# LEDs.net
KiCad netlist of a schematic drawn in Altium Designer
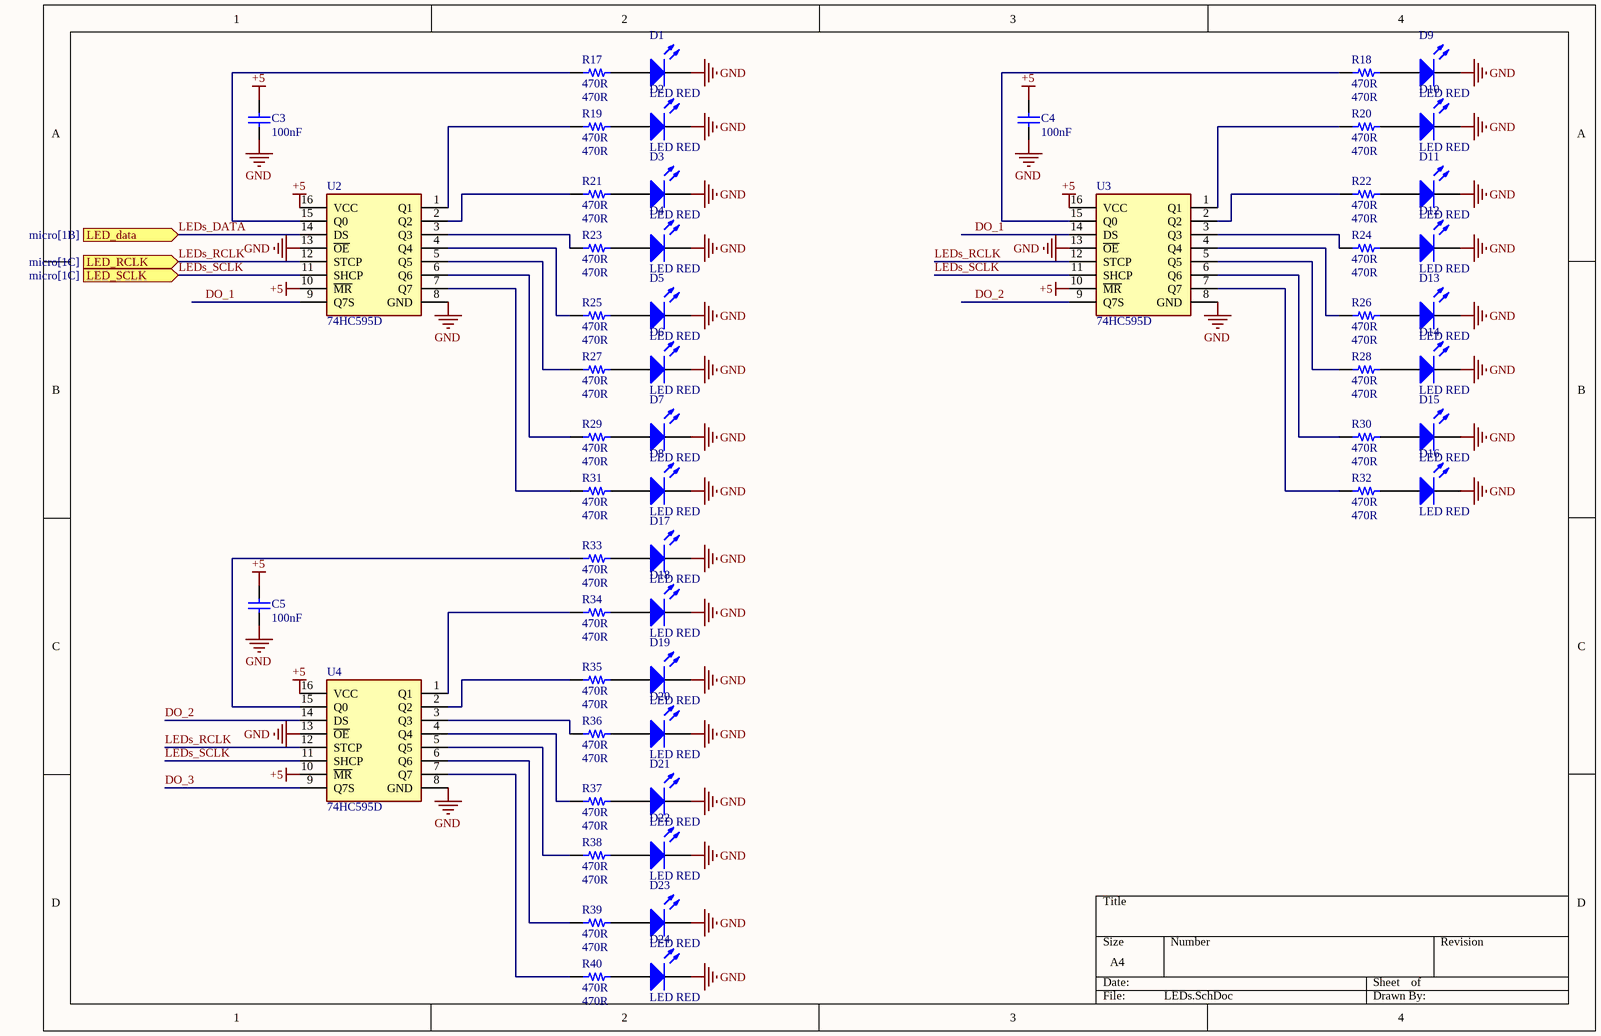
[diagram p0: LEDs.SchDoc]

(export (version "E")
  (design (tool "Eeschema 10.0.6"))
  (components
    (comp (ref "C3")
      (value "100nF")
      (footprint "SMD_CAP_0805")
      (description "CAP SMD 0805")
      (fields (field (name "PUBLISHER") "Altium Limited"))
      (libsource (lib "Miscellaneous Devices") (part "Cap"))
    )
    (comp (ref "C4")
      (value "100nF")
      (footprint "SMD_CAP_0805")
      (description "CAP SMD 0805")
      (fields (field (name "PUBLISHER") "Altium Limited"))
      (libsource (lib "Miscellaneous Devices") (part "Cap"))
    )
    (comp (ref "C5")
      (value "100nF")
      (footprint "SMD_CAP_0805")
      (description "CAP SMD 0805")
      (fields (field (name "PUBLISHER") "Altium Limited"))
      (libsource (lib "Miscellaneous Devices") (part "Cap"))
    )
    (comp (ref "D1")
      (value "LED RED")
      (footprint "LED_0805 G")
      (description "LED SMD 0805 RED")
      (fields (field (name "PUBLISHER") "Altium Limited"))
      (libsource (lib "Miscellaneous Devices") (part "LED0"))
    )
    (comp (ref "D2")
      (value "LED RED")
      (footprint "LED_0805 G")
      (description "LED SMD 0805 RED")
      (fields (field (name "PUBLISHER") "Altium Limited"))
      (libsource (lib "Miscellaneous Devices") (part "LED0"))
    )
    (comp (ref "D3")
      (value "LED RED")
      (footprint "LED_0805 G")
      (description "LED SMD 0805 RED")
      (fields (field (name "PUBLISHER") "Altium Limited"))
      (libsource (lib "Miscellaneous Devices") (part "LED0"))
    )
    (comp (ref "D4")
      (value "LED RED")
      (footprint "LED_0805 G")
      (description "LED SMD 0805 RED")
      (fields (field (name "PUBLISHER") "Altium Limited"))
      (libsource (lib "Miscellaneous Devices") (part "LED0"))
    )
    (comp (ref "D5")
      (value "LED RED")
      (footprint "LED_0805 G")
      (description "LED SMD 0805 RED")
      (fields (field (name "PUBLISHER") "Altium Limited"))
      (libsource (lib "Miscellaneous Devices") (part "LED0"))
    )
    (comp (ref "D6")
      (value "LED RED")
      (footprint "LED_0805 G")
      (description "LED SMD 0805 RED")
      (fields (field (name "PUBLISHER") "Altium Limited"))
      (libsource (lib "Miscellaneous Devices") (part "LED0"))
    )
    (comp (ref "D7")
      (value "LED RED")
      (footprint "LED_0805 G")
      (description "LED SMD 0805 RED")
      (fields (field (name "PUBLISHER") "Altium Limited"))
      (libsource (lib "Miscellaneous Devices") (part "LED0"))
    )
    (comp (ref "D8")
      (value "LED RED")
      (footprint "LED_0805 G")
      (description "LED SMD 0805 RED")
      (fields (field (name "PUBLISHER") "Altium Limited"))
      (libsource (lib "Miscellaneous Devices") (part "LED0"))
    )
    (comp (ref "D9")
      (value "LED RED")
      (footprint "LED_0805 G")
      (description "LED SMD 0805 RED")
      (fields (field (name "PUBLISHER") "Altium Limited"))
      (libsource (lib "Miscellaneous Devices") (part "LED0"))
    )
    (comp (ref "D10")
      (value "LED RED")
      (footprint "LED_0805 G")
      (description "LED SMD 0805 RED")
      (fields (field (name "PUBLISHER") "Altium Limited"))
      (libsource (lib "Miscellaneous Devices") (part "LED0"))
    )
    (comp (ref "D11")
      (value "LED RED")
      (footprint "LED_0805 G")
      (description "LED SMD 0805 RED")
      (fields (field (name "PUBLISHER") "Altium Limited"))
      (libsource (lib "Miscellaneous Devices") (part "LED0"))
    )
    (comp (ref "D12")
      (value "LED RED")
      (footprint "LED_0805 G")
      (description "LED SMD 0805 RED")
      (fields (field (name "PUBLISHER") "Altium Limited"))
      (libsource (lib "Miscellaneous Devices") (part "LED0"))
    )
    (comp (ref "D13")
      (value "LED RED")
      (footprint "LED_0805 G")
      (description "LED SMD 0805 RED")
      (fields (field (name "PUBLISHER") "Altium Limited"))
      (libsource (lib "Miscellaneous Devices") (part "LED0"))
    )
    (comp (ref "D14")
      (value "LED RED")
      (footprint "LED_0805 G")
      (description "LED SMD 0805 RED")
      (fields (field (name "PUBLISHER") "Altium Limited"))
      (libsource (lib "Miscellaneous Devices") (part "LED0"))
    )
    (comp (ref "D15")
      (value "LED RED")
      (footprint "LED_0805 G")
      (description "LED SMD 0805 RED")
      (fields (field (name "PUBLISHER") "Altium Limited"))
      (libsource (lib "Miscellaneous Devices") (part "LED0"))
    )
    (comp (ref "D16")
      (value "LED RED")
      (footprint "LED_0805 G")
      (description "LED SMD 0805 RED")
      (fields (field (name "PUBLISHER") "Altium Limited"))
      (libsource (lib "Miscellaneous Devices") (part "LED0"))
    )
    (comp (ref "D17")
      (value "LED RED")
      (footprint "LED_0805 G")
      (description "LED SMD 0805 RED")
      (fields (field (name "PUBLISHER") "Altium Limited"))
      (libsource (lib "Miscellaneous Devices") (part "LED0"))
    )
    (comp (ref "D18")
      (value "LED RED")
      (footprint "LED_0805 G")
      (description "LED SMD 0805 RED")
      (fields (field (name "PUBLISHER") "Altium Limited"))
      (libsource (lib "Miscellaneous Devices") (part "LED0"))
    )
    (comp (ref "D19")
      (value "LED RED")
      (footprint "LED_0805 G")
      (description "LED SMD 0805 RED")
      (fields (field (name "PUBLISHER") "Altium Limited"))
      (libsource (lib "Miscellaneous Devices") (part "LED0"))
    )
    (comp (ref "D20")
      (value "LED RED")
      (footprint "LED_0805 G")
      (description "LED SMD 0805 RED")
      (fields (field (name "PUBLISHER") "Altium Limited"))
      (libsource (lib "Miscellaneous Devices") (part "LED0"))
    )
    (comp (ref "D21")
      (value "LED RED")
      (footprint "LED_0805 G")
      (description "LED SMD 0805 RED")
      (fields (field (name "PUBLISHER") "Altium Limited"))
      (libsource (lib "Miscellaneous Devices") (part "LED0"))
    )
    (comp (ref "D22")
      (value "LED RED")
      (footprint "LED_0805 G")
      (description "LED SMD 0805 RED")
      (fields (field (name "PUBLISHER") "Altium Limited"))
      (libsource (lib "Miscellaneous Devices") (part "LED0"))
    )
    (comp (ref "D23")
      (value "LED RED")
      (footprint "LED_0805 G")
      (description "LED SMD 0805 RED")
      (fields (field (name "PUBLISHER") "Altium Limited"))
      (libsource (lib "Miscellaneous Devices") (part "LED0"))
    )
    (comp (ref "D24")
      (value "LED RED")
      (footprint "LED_0805 G")
      (description "LED SMD 0805 RED")
      (fields (field (name "PUBLISHER") "Altium Limited"))
      (libsource (lib "Miscellaneous Devices") (part "LED0"))
    )
    (comp (ref "R17")
      (value "470R")
      (footprint "RES0805")
      (description "RES SMD 0603")
      (fields (field (name "PART NUMBER") "RCS0805100KFKEA") (field (name "ALTIUM_VALUE") "470R"))
      (libsource (lib "lamp control-ver2") (part "Resistor"))
    )
    (comp (ref "R18")
      (value "470R")
      (footprint "RES0805")
      (description "RES SMD 0603")
      (fields (field (name "PART NUMBER") "RCS0805100KFKEA") (field (name "ALTIUM_VALUE") "470R"))
      (libsource (lib "lamp control-ver2") (part "Resistor"))
    )
    (comp (ref "R19")
      (value "470R")
      (footprint "RES0805")
      (description "RES SMD 0603")
      (fields (field (name "PART NUMBER") "RCS0805100KFKEA") (field (name "ALTIUM_VALUE") "470R"))
      (libsource (lib "lamp control-ver2") (part "Resistor"))
    )
    (comp (ref "R20")
      (value "470R")
      (footprint "RES0805")
      (description "RES SMD 0603")
      (fields (field (name "PART NUMBER") "RCS0805100KFKEA") (field (name "ALTIUM_VALUE") "470R"))
      (libsource (lib "lamp control-ver2") (part "Resistor"))
    )
    (comp (ref "R21")
      (value "470R")
      (footprint "RES0805")
      (description "RES SMD 0603")
      (fields (field (name "PART NUMBER") "RCS0805100KFKEA") (field (name "ALTIUM_VALUE") "470R"))
      (libsource (lib "lamp control-ver2") (part "Resistor"))
    )
    (comp (ref "R22")
      (value "470R")
      (footprint "RES0805")
      (description "RES SMD 0603")
      (fields (field (name "PART NUMBER") "RCS0805100KFKEA") (field (name "ALTIUM_VALUE") "470R"))
      (libsource (lib "lamp control-ver2") (part "Resistor"))
    )
    (comp (ref "R23")
      (value "470R")
      (footprint "RES0805")
      (description "RES SMD 0603")
      (fields (field (name "PART NUMBER") "RCS0805100KFKEA") (field (name "ALTIUM_VALUE") "470R"))
      (libsource (lib "lamp control-ver2") (part "Resistor"))
    )
    (comp (ref "R24")
      (value "470R")
      (footprint "RES0805")
      (description "RES SMD 0603")
      (fields (field (name "PART NUMBER") "RCS0805100KFKEA") (field (name "ALTIUM_VALUE") "470R"))
      (libsource (lib "lamp control-ver2") (part "Resistor"))
    )
    (comp (ref "R25")
      (value "470R")
      (footprint "RES0805")
      (description "RES SMD 0603")
      (fields (field (name "PART NUMBER") "RCS0805100KFKEA") (field (name "ALTIUM_VALUE") "470R"))
      (libsource (lib "lamp control-ver2") (part "Resistor"))
    )
    (comp (ref "R26")
      (value "470R")
      (footprint "RES0805")
      (description "RES SMD 0603")
      (fields (field (name "PART NUMBER") "RCS0805100KFKEA") (field (name "ALTIUM_VALUE") "470R"))
      (libsource (lib "lamp control-ver2") (part "Resistor"))
    )
    (comp (ref "R27")
      (value "470R")
      (footprint "RES0805")
      (description "RES SMD 0603")
      (fields (field (name "PART NUMBER") "RCS0805100KFKEA") (field (name "ALTIUM_VALUE") "470R"))
      (libsource (lib "lamp control-ver2") (part "Resistor"))
    )
    (comp (ref "R28")
      (value "470R")
      (footprint "RES0805")
      (description "RES SMD 0603")
      (fields (field (name "PART NUMBER") "RCS0805100KFKEA") (field (name "ALTIUM_VALUE") "470R"))
      (libsource (lib "lamp control-ver2") (part "Resistor"))
    )
    (comp (ref "R29")
      (value "470R")
      (footprint "RES0805")
      (description "RES SMD 0603")
      (fields (field (name "PART NUMBER") "RCS0805100KFKEA") (field (name "ALTIUM_VALUE") "470R"))
      (libsource (lib "lamp control-ver2") (part "Resistor"))
    )
    (comp (ref "R30")
      (value "470R")
      (footprint "RES0805")
      (description "RES SMD 0603")
      (fields (field (name "PART NUMBER") "RCS0805100KFKEA") (field (name "ALTIUM_VALUE") "470R"))
      (libsource (lib "lamp control-ver2") (part "Resistor"))
    )
    (comp (ref "R31")
      (value "470R")
      (footprint "RES0805")
      (description "RES SMD 0603")
      (fields (field (name "PART NUMBER") "RCS0805100KFKEA") (field (name "ALTIUM_VALUE") "470R"))
      (libsource (lib "lamp control-ver2") (part "Resistor"))
    )
    (comp (ref "R32")
      (value "470R")
      (footprint "RES0805")
      (description "RES SMD 0603")
      (fields (field (name "PART NUMBER") "RCS0805100KFKEA") (field (name "ALTIUM_VALUE") "470R"))
      (libsource (lib "lamp control-ver2") (part "Resistor"))
    )
    (comp (ref "R33")
      (value "470R")
      (footprint "RES0805")
      (description "RES SMD 0603")
      (fields (field (name "PART NUMBER") "RCS0805100KFKEA") (field (name "ALTIUM_VALUE") "470R"))
      (libsource (lib "lamp control-ver2") (part "Resistor"))
    )
    (comp (ref "R34")
      (value "470R")
      (footprint "RES0805")
      (description "RES SMD 0603")
      (fields (field (name "PART NUMBER") "RCS0805100KFKEA") (field (name "ALTIUM_VALUE") "470R"))
      (libsource (lib "lamp control-ver2") (part "Resistor"))
    )
    (comp (ref "R35")
      (value "470R")
      (footprint "RES0805")
      (description "RES SMD 0603")
      (fields (field (name "PART NUMBER") "RCS0805100KFKEA") (field (name "ALTIUM_VALUE") "470R"))
      (libsource (lib "lamp control-ver2") (part "Resistor"))
    )
    (comp (ref "R36")
      (value "470R")
      (footprint "RES0805")
      (description "RES SMD 0603")
      (fields (field (name "PART NUMBER") "RCS0805100KFKEA") (field (name "ALTIUM_VALUE") "470R"))
      (libsource (lib "lamp control-ver2") (part "Resistor"))
    )
    (comp (ref "R37")
      (value "470R")
      (footprint "RES0805")
      (description "RES SMD 0603")
      (fields (field (name "PART NUMBER") "RCS0805100KFKEA") (field (name "ALTIUM_VALUE") "470R"))
      (libsource (lib "lamp control-ver2") (part "Resistor"))
    )
    (comp (ref "R38")
      (value "470R")
      (footprint "RES0805")
      (description "RES SMD 0603")
      (fields (field (name "PART NUMBER") "RCS0805100KFKEA") (field (name "ALTIUM_VALUE") "470R"))
      (libsource (lib "lamp control-ver2") (part "Resistor"))
    )
    (comp (ref "R39")
      (value "470R")
      (footprint "RES0805")
      (description "RES SMD 0603")
      (fields (field (name "PART NUMBER") "RCS0805100KFKEA") (field (name "ALTIUM_VALUE") "470R"))
      (libsource (lib "lamp control-ver2") (part "Resistor"))
    )
    (comp (ref "R40")
      (value "470R")
      (footprint "RES0805")
      (description "RES SMD 0603")
      (fields (field (name "PART NUMBER") "RCS0805100KFKEA") (field (name "ALTIUM_VALUE") "470R"))
      (libsource (lib "lamp control-ver2") (part "Resistor"))
    )
    (comp (ref "U2")
      (value "74HC595D")
      (footprint "SOIC127P600X175-16N")
      (description "74HC595 SMD")
      (libsource (lib "*") (part "74HC595D"))
    )
    (comp (ref "U3")
      (value "74HC595D")
      (footprint "SOIC127P600X175-16N")
      (description "74HC595 SMD")
      (libsource (lib "*") (part "74HC595D"))
    )
    (comp (ref "U4")
      (value "74HC595D")
      (footprint "SOIC127P600X175-16N")
      (description "74HC595 SMD")
      (libsource (lib "*") (part "74HC595D"))
    )
  )
  (nets
    (net (code "1") (name "+5") (class "Default")
      (node (ref "C3") (pin "2") (pinfunction "2_2") (pintype "passive"))
      (node (ref "C4") (pin "2") (pinfunction "2_2") (pintype "passive"))
      (node (ref "C5") (pin "2") (pinfunction "2_2") (pintype "passive"))
      (node (ref "U2") (pin "10") (pinfunction "~{MR}_10") (pintype "passive"))
      (node (ref "U2") (pin "16") (pinfunction "VCC_16") (pintype "passive"))
      (node (ref "U3") (pin "10") (pinfunction "~{MR}_10") (pintype "passive"))
      (node (ref "U3") (pin "16") (pinfunction "VCC_16") (pintype "passive"))
      (node (ref "U4") (pin "10") (pinfunction "~{MR}_10") (pintype "passive"))
      (node (ref "U4") (pin "16") (pinfunction "VCC_16") (pintype "passive"))
    )
    (net (code "2") (name "/DO_1") (class "Default")
      (node (ref "U2") (pin "9") (pinfunction "Q7S_9") (pintype "passive"))
      (node (ref "U3") (pin "14") (pinfunction "DS_14") (pintype "passive"))
    )
    (net (code "3") (name "/DO_2") (class "Default")
      (node (ref "U3") (pin "9") (pinfunction "Q7S_9") (pintype "passive"))
      (node (ref "U4") (pin "14") (pinfunction "DS_14") (pintype "passive"))
    )
    (net (code "4") (name "/DO_3") (class "Default")
      (node (ref "U4") (pin "9") (pinfunction "Q7S_9") (pintype "passive"))
    )
    (net (code "5") (name "/LEDs_DATA") (class "Default")
      (node (ref "U2") (pin "14") (pinfunction "DS_14") (pintype "passive"))
    )
    (net (code "6") (name "/LEDs_RCLK") (class "Default")
      (node (ref "U2") (pin "12") (pinfunction "STCP_12") (pintype "passive"))
      (node (ref "U3") (pin "12") (pinfunction "STCP_12") (pintype "passive"))
      (node (ref "U4") (pin "12") (pinfunction "STCP_12") (pintype "passive"))
    )
    (net (code "7") (name "/LEDs_SCLK") (class "Default")
      (node (ref "U2") (pin "11") (pinfunction "SHCP_11") (pintype "passive"))
      (node (ref "U3") (pin "11") (pinfunction "SHCP_11") (pintype "passive"))
      (node (ref "U4") (pin "11") (pinfunction "SHCP_11") (pintype "passive"))
    )
    (net (code "8") (name "GND") (class "Default")
      (node (ref "C3") (pin "1") (pinfunction "1_1") (pintype "passive"))
      (node (ref "C4") (pin "1") (pinfunction "1_1") (pintype "passive"))
      (node (ref "C5") (pin "1") (pinfunction "1_1") (pintype "passive"))
      (node (ref "D1") (pin "2") (pinfunction "K_2") (pintype "passive"))
      (node (ref "D10") (pin "2") (pinfunction "K_2") (pintype "passive"))
      (node (ref "D11") (pin "2") (pinfunction "K_2") (pintype "passive"))
      (node (ref "D12") (pin "2") (pinfunction "K_2") (pintype "passive"))
      (node (ref "D13") (pin "2") (pinfunction "K_2") (pintype "passive"))
      (node (ref "D14") (pin "2") (pinfunction "K_2") (pintype "passive"))
      (node (ref "D15") (pin "2") (pinfunction "K_2") (pintype "passive"))
      (node (ref "D16") (pin "2") (pinfunction "K_2") (pintype "passive"))
      (node (ref "D17") (pin "2") (pinfunction "K_2") (pintype "passive"))
      (node (ref "D18") (pin "2") (pinfunction "K_2") (pintype "passive"))
      (node (ref "D19") (pin "2") (pinfunction "K_2") (pintype "passive"))
      (node (ref "D2") (pin "2") (pinfunction "K_2") (pintype "passive"))
      (node (ref "D20") (pin "2") (pinfunction "K_2") (pintype "passive"))
      (node (ref "D21") (pin "2") (pinfunction "K_2") (pintype "passive"))
      (node (ref "D22") (pin "2") (pinfunction "K_2") (pintype "passive"))
      (node (ref "D23") (pin "2") (pinfunction "K_2") (pintype "passive"))
      (node (ref "D24") (pin "2") (pinfunction "K_2") (pintype "passive"))
      (node (ref "D3") (pin "2") (pinfunction "K_2") (pintype "passive"))
      (node (ref "D4") (pin "2") (pinfunction "K_2") (pintype "passive"))
      (node (ref "D5") (pin "2") (pinfunction "K_2") (pintype "passive"))
      (node (ref "D6") (pin "2") (pinfunction "K_2") (pintype "passive"))
      (node (ref "D7") (pin "2") (pinfunction "K_2") (pintype "passive"))
      (node (ref "D8") (pin "2") (pinfunction "K_2") (pintype "passive"))
      (node (ref "D9") (pin "2") (pinfunction "K_2") (pintype "passive"))
      (node (ref "U2") (pin "13") (pinfunction "~{OE}_13") (pintype "passive"))
      (node (ref "U2") (pin "8") (pinfunction "GND_8") (pintype "passive"))
      (node (ref "U3") (pin "13") (pinfunction "~{OE}_13") (pintype "passive"))
      (node (ref "U3") (pin "8") (pinfunction "GND_8") (pintype "passive"))
      (node (ref "U4") (pin "13") (pinfunction "~{OE}_13") (pintype "passive"))
      (node (ref "U4") (pin "8") (pinfunction "GND_8") (pintype "passive"))
    )
    (net (code "9") (name "Net-(D1-A)") (class "Default")
      (node (ref "D1") (pin "1") (pinfunction "A_1") (pintype "passive"))
      (node (ref "R17") (pin "1") (pinfunction "1_1") (pintype "passive"))
    )
    (net (code "10") (name "Net-(D2-A)") (class "Default")
      (node (ref "D2") (pin "1") (pinfunction "A_1") (pintype "passive"))
      (node (ref "R19") (pin "1") (pinfunction "1_1") (pintype "passive"))
    )
    (net (code "11") (name "Net-(D3-A)") (class "Default")
      (node (ref "D3") (pin "1") (pinfunction "A_1") (pintype "passive"))
      (node (ref "R21") (pin "1") (pinfunction "1_1") (pintype "passive"))
    )
    (net (code "12") (name "Net-(D4-A)") (class "Default")
      (node (ref "D4") (pin "1") (pinfunction "A_1") (pintype "passive"))
      (node (ref "R23") (pin "1") (pinfunction "1_1") (pintype "passive"))
    )
    (net (code "13") (name "Net-(D5-A)") (class "Default")
      (node (ref "D5") (pin "1") (pinfunction "A_1") (pintype "passive"))
      (node (ref "R25") (pin "1") (pinfunction "1_1") (pintype "passive"))
    )
    (net (code "14") (name "Net-(D6-A)") (class "Default")
      (node (ref "D6") (pin "1") (pinfunction "A_1") (pintype "passive"))
      (node (ref "R27") (pin "1") (pinfunction "1_1") (pintype "passive"))
    )
    (net (code "15") (name "Net-(D7-A)") (class "Default")
      (node (ref "D7") (pin "1") (pinfunction "A_1") (pintype "passive"))
      (node (ref "R29") (pin "1") (pinfunction "1_1") (pintype "passive"))
    )
    (net (code "16") (name "Net-(D8-A)") (class "Default")
      (node (ref "D8") (pin "1") (pinfunction "A_1") (pintype "passive"))
      (node (ref "R31") (pin "1") (pinfunction "1_1") (pintype "passive"))
    )
    (net (code "17") (name "Net-(D9-A)") (class "Default")
      (node (ref "D9") (pin "1") (pinfunction "A_1") (pintype "passive"))
      (node (ref "R18") (pin "1") (pinfunction "1_1") (pintype "passive"))
    )
    (net (code "18") (name "Net-(D10-A)") (class "Default")
      (node (ref "D10") (pin "1") (pinfunction "A_1") (pintype "passive"))
      (node (ref "R20") (pin "1") (pinfunction "1_1") (pintype "passive"))
    )
    (net (code "19") (name "Net-(D11-A)") (class "Default")
      (node (ref "D11") (pin "1") (pinfunction "A_1") (pintype "passive"))
      (node (ref "R22") (pin "1") (pinfunction "1_1") (pintype "passive"))
    )
    (net (code "20") (name "Net-(D12-A)") (class "Default")
      (node (ref "D12") (pin "1") (pinfunction "A_1") (pintype "passive"))
      (node (ref "R24") (pin "1") (pinfunction "1_1") (pintype "passive"))
    )
    (net (code "21") (name "Net-(D13-A)") (class "Default")
      (node (ref "D13") (pin "1") (pinfunction "A_1") (pintype "passive"))
      (node (ref "R26") (pin "1") (pinfunction "1_1") (pintype "passive"))
    )
    (net (code "22") (name "Net-(D14-A)") (class "Default")
      (node (ref "D14") (pin "1") (pinfunction "A_1") (pintype "passive"))
      (node (ref "R28") (pin "1") (pinfunction "1_1") (pintype "passive"))
    )
    (net (code "23") (name "Net-(D15-A)") (class "Default")
      (node (ref "D15") (pin "1") (pinfunction "A_1") (pintype "passive"))
      (node (ref "R30") (pin "1") (pinfunction "1_1") (pintype "passive"))
    )
    (net (code "24") (name "Net-(D16-A)") (class "Default")
      (node (ref "D16") (pin "1") (pinfunction "A_1") (pintype "passive"))
      (node (ref "R32") (pin "1") (pinfunction "1_1") (pintype "passive"))
    )
    (net (code "25") (name "Net-(D17-A)") (class "Default")
      (node (ref "D17") (pin "1") (pinfunction "A_1") (pintype "passive"))
      (node (ref "R33") (pin "1") (pinfunction "1_1") (pintype "passive"))
    )
    (net (code "26") (name "Net-(D18-A)") (class "Default")
      (node (ref "D18") (pin "1") (pinfunction "A_1") (pintype "passive"))
      (node (ref "R34") (pin "1") (pinfunction "1_1") (pintype "passive"))
    )
    (net (code "27") (name "Net-(D19-A)") (class "Default")
      (node (ref "D19") (pin "1") (pinfunction "A_1") (pintype "passive"))
      (node (ref "R35") (pin "1") (pinfunction "1_1") (pintype "passive"))
    )
    (net (code "28") (name "Net-(D20-A)") (class "Default")
      (node (ref "D20") (pin "1") (pinfunction "A_1") (pintype "passive"))
      (node (ref "R36") (pin "1") (pinfunction "1_1") (pintype "passive"))
    )
    (net (code "29") (name "Net-(D21-A)") (class "Default")
      (node (ref "D21") (pin "1") (pinfunction "A_1") (pintype "passive"))
      (node (ref "R37") (pin "1") (pinfunction "1_1") (pintype "passive"))
    )
    (net (code "30") (name "Net-(D22-A)") (class "Default")
      (node (ref "D22") (pin "1") (pinfunction "A_1") (pintype "passive"))
      (node (ref "R38") (pin "1") (pinfunction "1_1") (pintype "passive"))
    )
    (net (code "31") (name "Net-(D23-A)") (class "Default")
      (node (ref "D23") (pin "1") (pinfunction "A_1") (pintype "passive"))
      (node (ref "R39") (pin "1") (pinfunction "1_1") (pintype "passive"))
    )
    (net (code "32") (name "Net-(D24-A)") (class "Default")
      (node (ref "D24") (pin "1") (pinfunction "A_1") (pintype "passive"))
      (node (ref "R40") (pin "1") (pinfunction "1_1") (pintype "passive"))
    )
    (net (code "33") (name "Net-(U2-Q0)") (class "Default")
      (node (ref "R17") (pin "2") (pinfunction "2_2") (pintype "passive"))
      (node (ref "U2") (pin "15") (pinfunction "Q0_15") (pintype "passive"))
    )
    (net (code "34") (name "Net-(U2-Q1)") (class "Default")
      (node (ref "R19") (pin "2") (pinfunction "2_2") (pintype "passive"))
      (node (ref "U2") (pin "1") (pinfunction "Q1_1") (pintype "passive"))
    )
    (net (code "35") (name "Net-(U2-Q2)") (class "Default")
      (node (ref "R21") (pin "2") (pinfunction "2_2") (pintype "passive"))
      (node (ref "U2") (pin "2") (pinfunction "Q2_2") (pintype "passive"))
    )
    (net (code "36") (name "Net-(U2-Q3)") (class "Default")
      (node (ref "R23") (pin "2") (pinfunction "2_2") (pintype "passive"))
      (node (ref "U2") (pin "3") (pinfunction "Q3_3") (pintype "passive"))
    )
    (net (code "37") (name "Net-(U2-Q4)") (class "Default")
      (node (ref "R25") (pin "2") (pinfunction "2_2") (pintype "passive"))
      (node (ref "U2") (pin "4") (pinfunction "Q4_4") (pintype "passive"))
    )
    (net (code "38") (name "Net-(U2-Q5)") (class "Default")
      (node (ref "R27") (pin "2") (pinfunction "2_2") (pintype "passive"))
      (node (ref "U2") (pin "5") (pinfunction "Q5_5") (pintype "passive"))
    )
    (net (code "39") (name "Net-(U2-Q6)") (class "Default")
      (node (ref "R29") (pin "2") (pinfunction "2_2") (pintype "passive"))
      (node (ref "U2") (pin "6") (pinfunction "Q6_6") (pintype "passive"))
    )
    (net (code "40") (name "Net-(U2-Q7)") (class "Default")
      (node (ref "R31") (pin "2") (pinfunction "2_2") (pintype "passive"))
      (node (ref "U2") (pin "7") (pinfunction "Q7_7") (pintype "passive"))
    )
    (net (code "41") (name "Net-(U3-Q0)") (class "Default")
      (node (ref "R18") (pin "2") (pinfunction "2_2") (pintype "passive"))
      (node (ref "U3") (pin "15") (pinfunction "Q0_15") (pintype "passive"))
    )
    (net (code "42") (name "Net-(U3-Q1)") (class "Default")
      (node (ref "R20") (pin "2") (pinfunction "2_2") (pintype "passive"))
      (node (ref "U3") (pin "1") (pinfunction "Q1_1") (pintype "passive"))
    )
    (net (code "43") (name "Net-(U3-Q2)") (class "Default")
      (node (ref "R22") (pin "2") (pinfunction "2_2") (pintype "passive"))
      (node (ref "U3") (pin "2") (pinfunction "Q2_2") (pintype "passive"))
    )
    (net (code "44") (name "Net-(U3-Q3)") (class "Default")
      (node (ref "R24") (pin "2") (pinfunction "2_2") (pintype "passive"))
      (node (ref "U3") (pin "3") (pinfunction "Q3_3") (pintype "passive"))
    )
    (net (code "45") (name "Net-(U3-Q4)") (class "Default")
      (node (ref "R26") (pin "2") (pinfunction "2_2") (pintype "passive"))
      (node (ref "U3") (pin "4") (pinfunction "Q4_4") (pintype "passive"))
    )
    (net (code "46") (name "Net-(U3-Q5)") (class "Default")
      (node (ref "R28") (pin "2") (pinfunction "2_2") (pintype "passive"))
      (node (ref "U3") (pin "5") (pinfunction "Q5_5") (pintype "passive"))
    )
    (net (code "47") (name "Net-(U3-Q6)") (class "Default")
      (node (ref "R30") (pin "2") (pinfunction "2_2") (pintype "passive"))
      (node (ref "U3") (pin "6") (pinfunction "Q6_6") (pintype "passive"))
    )
    (net (code "48") (name "Net-(U3-Q7)") (class "Default")
      (node (ref "R32") (pin "2") (pinfunction "2_2") (pintype "passive"))
      (node (ref "U3") (pin "7") (pinfunction "Q7_7") (pintype "passive"))
    )
    (net (code "49") (name "Net-(U4-Q0)") (class "Default")
      (node (ref "R33") (pin "2") (pinfunction "2_2") (pintype "passive"))
      (node (ref "U4") (pin "15") (pinfunction "Q0_15") (pintype "passive"))
    )
    (net (code "50") (name "Net-(U4-Q1)") (class "Default")
      (node (ref "R34") (pin "2") (pinfunction "2_2") (pintype "passive"))
      (node (ref "U4") (pin "1") (pinfunction "Q1_1") (pintype "passive"))
    )
    (net (code "51") (name "Net-(U4-Q2)") (class "Default")
      (node (ref "R35") (pin "2") (pinfunction "2_2") (pintype "passive"))
      (node (ref "U4") (pin "2") (pinfunction "Q2_2") (pintype "passive"))
    )
    (net (code "52") (name "Net-(U4-Q3)") (class "Default")
      (node (ref "R36") (pin "2") (pinfunction "2_2") (pintype "passive"))
      (node (ref "U4") (pin "3") (pinfunction "Q3_3") (pintype "passive"))
    )
    (net (code "53") (name "Net-(U4-Q4)") (class "Default")
      (node (ref "R37") (pin "2") (pinfunction "2_2") (pintype "passive"))
      (node (ref "U4") (pin "4") (pinfunction "Q4_4") (pintype "passive"))
    )
    (net (code "54") (name "Net-(U4-Q5)") (class "Default")
      (node (ref "R38") (pin "2") (pinfunction "2_2") (pintype "passive"))
      (node (ref "U4") (pin "5") (pinfunction "Q5_5") (pintype "passive"))
    )
    (net (code "55") (name "Net-(U4-Q6)") (class "Default")
      (node (ref "R39") (pin "2") (pinfunction "2_2") (pintype "passive"))
      (node (ref "U4") (pin "6") (pinfunction "Q6_6") (pintype "passive"))
    )
    (net (code "56") (name "Net-(U4-Q7)") (class "Default")
      (node (ref "R40") (pin "2") (pinfunction "2_2") (pintype "passive"))
      (node (ref "U4") (pin "7") (pinfunction "Q7_7") (pintype "passive"))
    )
  )
)
